# 9vpwr.net
KiCad netlist of a schematic drawn in Altium Designer
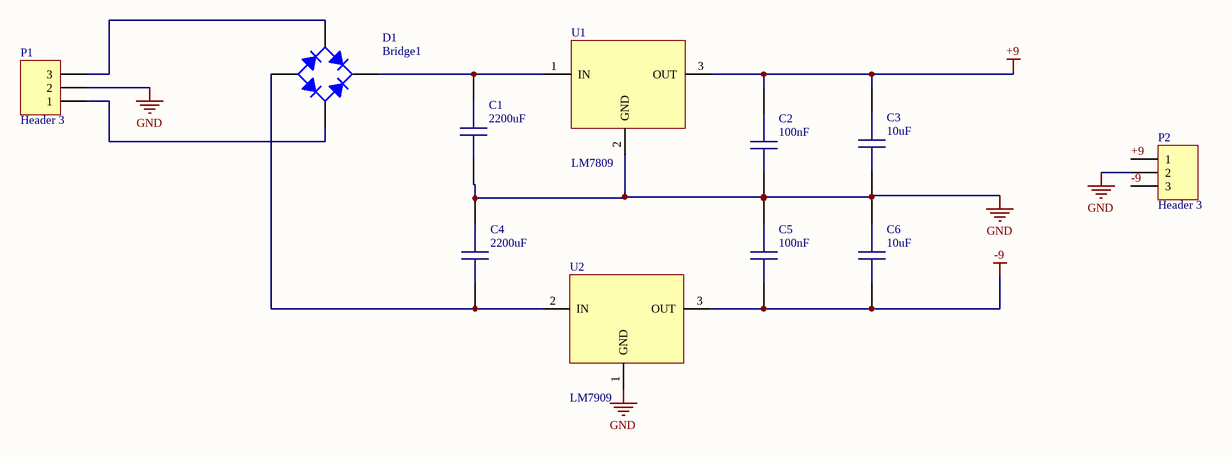
[diagram p0: 9vpwr.SchDoc]

(export (version "E")
  (design (tool "Eeschema 10.0.6"))
  (components
    (comp (ref "C1") (value "2200uF") (footprint "Cap NP") (libsource (lib "Funcgen") (part "Cap_NP")))
    (comp (ref "C2") (value "100nF") (footprint "Cap NP") (libsource (lib "Funcgen") (part "Cap_NP")))
    (comp (ref "C3") (value "10uF") (footprint "Cap NP") (libsource (lib "Funcgen") (part "Cap_NP")))
    (comp (ref "C4") (value "2200uF") (footprint "Cap NP") (libsource (lib "Funcgen") (part "Cap_NP")))
    (comp (ref "C5") (value "100nF") (footprint "Cap NP") (libsource (lib "Funcgen") (part "Cap_NP")))
    (comp (ref "C6") (value "10uF") (footprint "Cap NP") (libsource (lib "Funcgen") (part "Cap_NP")))
    (comp (ref "D1")
      (value "Bridge1")
      (footprint "D-38")
      (description "Full Wave Diode Bridge")
      (fields (field (name "PUBLISHER") "Altium Limited"))
      (libsource (lib "Miscellaneous Devices") (part "Bridge1"))
    )
    (comp (ref "P1")
      (value "Header 3")
      (footprint "HDR1X3")
      (description "Header, 3-Pin")
      (fields (field (name "PUBLISHER") "Altium Limited"))
      (libsource (lib "Miscellaneous Connectors") (part "Header 3"))
    )
    (comp (ref "P2")
      (value "Header 3")
      (footprint "HDR1X3")
      (description "Header, 3-Pin")
      (fields (field (name "PUBLISHER") "Altium Limited"))
      (libsource (lib "") (part "Header 3_1"))
    )
    (comp (ref "U1") (value "LM7809") (footprint "TIP 31") (libsource (lib "Funcgen") (part "LM7809")))
    (comp (ref "U2") (value "LM7909") (footprint "TIP 31") (libsource (lib "Funcgen") (part "LM7909")))
  )
  (nets
    (net (code "1") (name "+9") (class "Default")
      (node (ref "C2") (pin "2") (pinfunction "2_2") (pintype "passive"))
      (node (ref "C3") (pin "2") (pinfunction "2_2") (pintype "passive"))
      (node (ref "P2") (pin "1") (pinfunction "1_1") (pintype "passive"))
      (node (ref "U1") (pin "3") (pinfunction "OUT_3") (pintype "passive"))
    )
    (net (code "2") (name "-9") (class "Default")
      (node (ref "C5") (pin "1") (pinfunction "1_1") (pintype "passive"))
      (node (ref "C6") (pin "1") (pinfunction "1_1") (pintype "passive"))
      (node (ref "P2") (pin "3") (pinfunction "3_3") (pintype "passive"))
      (node (ref "U2") (pin "3") (pinfunction "OUT_3") (pintype "passive"))
    )
    (net (code "3") (name "GND") (class "Default")
      (node (ref "C1") (pin "1") (pinfunction "1_1") (pintype "passive"))
      (node (ref "C2") (pin "1") (pinfunction "1_1") (pintype "passive"))
      (node (ref "C3") (pin "1") (pinfunction "1_1") (pintype "passive"))
      (node (ref "C4") (pin "2") (pinfunction "2_2") (pintype "passive"))
      (node (ref "C5") (pin "2") (pinfunction "2_2") (pintype "passive"))
      (node (ref "C6") (pin "2") (pinfunction "2_2") (pintype "passive"))
      (node (ref "P1") (pin "2") (pinfunction "2_2") (pintype "passive"))
      (node (ref "P2") (pin "2") (pinfunction "2_2") (pintype "passive"))
      (node (ref "U1") (pin "2") (pinfunction "GND_2") (pintype "passive"))
      (node (ref "U2") (pin "1") (pinfunction "GND_1") (pintype "passive"))
    )
    (net (code "4") (name "Net-(D1-A)") (class "Default")
      (node (ref "C4") (pin "1") (pinfunction "1_1") (pintype "passive"))
      (node (ref "D1") (pin "3") (pinfunction "A_3") (pintype "passive"))
      (node (ref "U2") (pin "2") (pinfunction "IN_2") (pintype "passive"))
    )
    (net (code "5") (name "Net-(D1-C-Pad2)") (class "Default")
      (node (ref "D1") (pin "2") (pinfunction "C_2") (pintype "passive"))
      (node (ref "P1") (pin "1") (pinfunction "1_1") (pintype "passive"))
    )
    (net (code "6") (name "Net-(D1-C-Pad4)") (class "Default")
      (node (ref "D1") (pin "4") (pinfunction "C_4") (pintype "passive"))
      (node (ref "P1") (pin "3") (pinfunction "3_3") (pintype "passive"))
    )
    (net (code "7") (name "Net-(D1-K)") (class "Default")
      (node (ref "C1") (pin "2") (pinfunction "2_2") (pintype "passive"))
      (node (ref "D1") (pin "1") (pinfunction "K_1") (pintype "passive"))
      (node (ref "U1") (pin "1") (pinfunction "IN_1") (pintype "passive"))
    )
  )
)
